# LCD-0_2.net
KiCad netlist of a schematic drawn in EAGLE
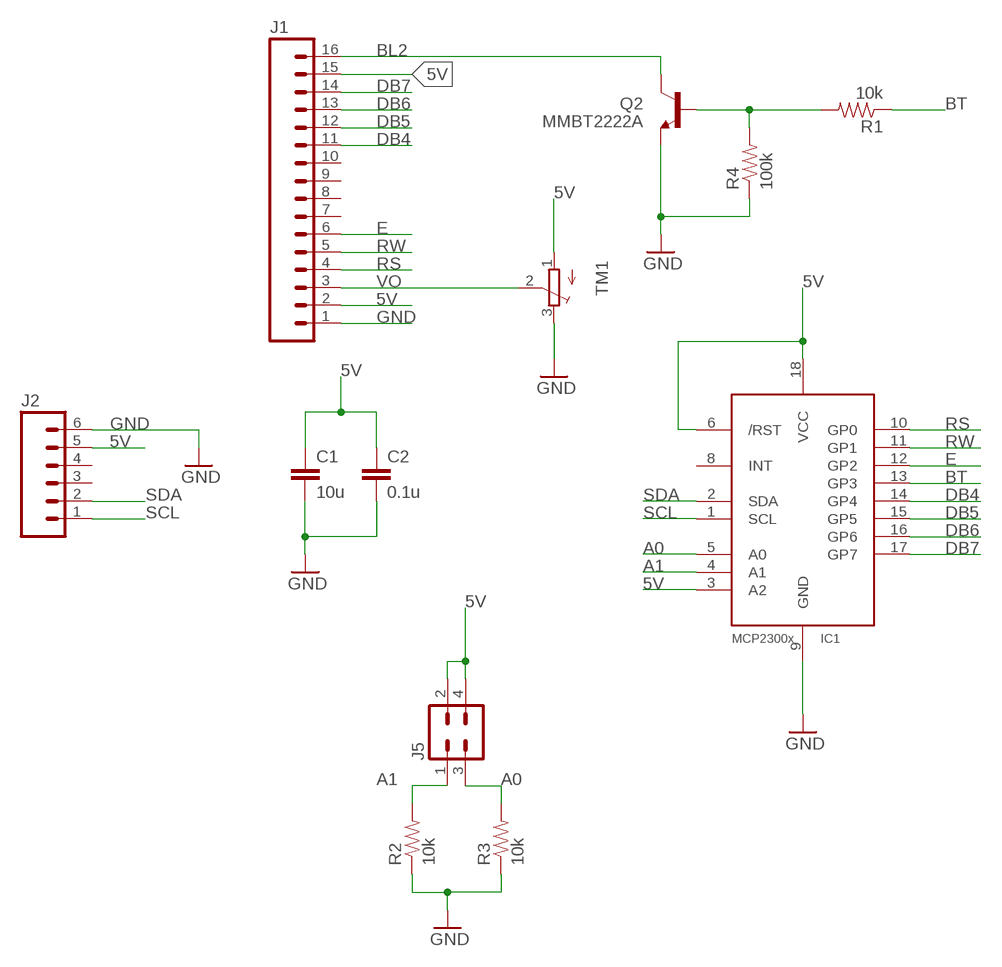
[diagram p0: schematic, sheet 1]

(export (version "E")
  (design (tool "Eeschema 10.0.6"))
  (components
    (comp (ref "C1")
      (value "10u")
      (footprint "eagle-import:0603-CAP")
      (libsource (lib "eagle-import") (part "CAP0603-CAP"))
    )
    (comp (ref "C2")
      (value "0.1u")
      (footprint "eagle-import:0603-CAP")
      (libsource (lib "eagle-import") (part "CAP0603-CAP"))
    )
    (comp (ref "IC1")
      (value "MCP23008/SO")
      (footprint "eagle-import:SO18W")
      (libsource (lib "eagle-import") (part "MCP23008/SO"))
    )
    (comp (ref "J1")
      (value "M16PTH")
      (footprint "eagle-import:1X16")
      (libsource (lib "eagle-import") (part "M16PTH"))
    )
    (comp (ref "J2")
      (value "M06RJ11")
      (footprint "eagle-import:RJ11-6P6C")
      (libsource (lib "eagle-import") (part "M06RJ11"))
    )
    (comp (ref "J5")
      (value "M02X2")
      (footprint "eagle-import:2X2")
      (libsource (lib "eagle-import") (part "M02X2"))
    )
    (comp (ref "Q2")
      (value "MMBT2222A")
      (footprint "eagle-import:SOT23-3")
      (libsource (lib "eagle-import") (part "TRANSISTOR_NPNMMBT2222A"))
    )
    (comp (ref "R1")
      (value "10k")
      (footprint "eagle-import:0603-RES")
      (libsource (lib "eagle-import") (part "RESISTOR0603"))
    )
    (comp (ref "R2")
      (value "10k")
      (footprint "eagle-import:0603-RES")
      (libsource (lib "eagle-import") (part "RESISTOR0603"))
    )
    (comp (ref "R3")
      (value "10k")
      (footprint "eagle-import:0603-RES")
      (libsource (lib "eagle-import") (part "RESISTOR0603"))
    )
    (comp (ref "R4")
      (value "100k")
      (footprint "eagle-import:0603-RES")
      (libsource (lib "eagle-import") (part "RESISTOR0603"))
    )
    (comp (ref "TM1")
      (value "TRIMPOTTC33X")
      (footprint "eagle-import:TC33X")
      (libsource (lib "eagle-import") (part "TRIMPOTTC33X"))
    )
  )
  (nets
    (net (code "1") (name "/A0") (class "Default")
      (node (ref "IC1") (pin "5") (pinfunction "A0_5") (pintype "input"))
      (node (ref "J5") (pin "3") (pinfunction "3_3") (pintype "passive"))
      (node (ref "R3") (pin "2") (pinfunction "2_2") (pintype "passive"))
    )
    (net (code "2") (name "/A1") (class "Default")
      (node (ref "IC1") (pin "4") (pinfunction "A1_4") (pintype "input"))
      (node (ref "J5") (pin "1") (pinfunction "1_1") (pintype "passive"))
      (node (ref "R2") (pin "2") (pinfunction "2_2") (pintype "passive"))
    )
    (net (code "3") (name "/BL2") (class "Default")
      (node (ref "J1") (pin "16") (pinfunction "16_16") (pintype "passive"))
      (node (ref "Q2") (pin "3") (pinfunction "C_3") (pintype "passive"))
    )
    (net (code "4") (name "/BT") (class "Default")
      (node (ref "IC1") (pin "13") (pinfunction "GP3_13") (pintype "bidirectional"))
      (node (ref "R1") (pin "1") (pinfunction "1_1") (pintype "passive"))
    )
    (net (code "5") (name "/DB4") (class "Default")
      (node (ref "IC1") (pin "14") (pinfunction "GP4_14") (pintype "bidirectional"))
      (node (ref "J1") (pin "11") (pinfunction "11_11") (pintype "passive"))
    )
    (net (code "6") (name "/DB5") (class "Default")
      (node (ref "IC1") (pin "15") (pinfunction "GP5_15") (pintype "bidirectional"))
      (node (ref "J1") (pin "12") (pinfunction "12_12") (pintype "passive"))
    )
    (net (code "7") (name "/DB6") (class "Default")
      (node (ref "IC1") (pin "16") (pinfunction "GP6_16") (pintype "bidirectional"))
      (node (ref "J1") (pin "13") (pinfunction "13_13") (pintype "passive"))
    )
    (net (code "8") (name "/DB7") (class "Default")
      (node (ref "IC1") (pin "17") (pinfunction "GP7_17") (pintype "bidirectional"))
      (node (ref "J1") (pin "14") (pinfunction "14_14") (pintype "passive"))
    )
    (net (code "9") (name "/E") (class "Default")
      (node (ref "IC1") (pin "12") (pinfunction "GP2_12") (pintype "bidirectional"))
      (node (ref "J1") (pin "6") (pinfunction "6_6") (pintype "passive"))
    )
    (net (code "10") (name "/RS") (class "Default")
      (node (ref "IC1") (pin "10") (pinfunction "GP0_10") (pintype "bidirectional"))
      (node (ref "J1") (pin "4") (pinfunction "4_4") (pintype "passive"))
    )
    (net (code "11") (name "/RW") (class "Default")
      (node (ref "IC1") (pin "11") (pinfunction "GP1_11") (pintype "bidirectional"))
      (node (ref "J1") (pin "5") (pinfunction "5_5") (pintype "passive"))
    )
    (net (code "12") (name "/SCL") (class "Default")
      (node (ref "IC1") (pin "1") (pinfunction "SCL_1") (pintype "bidirectional"))
      (node (ref "J2") (pin "1") (pinfunction "1_1") (pintype "passive"))
    )
    (net (code "13") (name "/SDA") (class "Default")
      (node (ref "IC1") (pin "2") (pinfunction "SDA_2") (pintype "bidirectional"))
      (node (ref "J2") (pin "2") (pinfunction "2_2") (pintype "passive"))
    )
    (net (code "14") (name "/VO") (class "Default")
      (node (ref "J1") (pin "3") (pinfunction "3_3") (pintype "passive"))
      (node (ref "TM1") (pin "2") (pinfunction "S_2") (pintype "passive"))
    )
    (net (code "15") (name "5V") (class "Default")
      (node (ref "C1") (pin "1") (pinfunction "1_1") (pintype "passive"))
      (node (ref "C2") (pin "1") (pinfunction "1_1") (pintype "passive"))
      (node (ref "IC1") (pin "18") (pinfunction "VCC_18") (pintype "power_in"))
      (node (ref "IC1") (pin "3") (pinfunction "A2_3") (pintype "input"))
      (node (ref "IC1") (pin "6") (pinfunction "/RST_6") (pintype "input"))
      (node (ref "J1") (pin "15") (pinfunction "15_15") (pintype "passive"))
      (node (ref "J1") (pin "2") (pinfunction "2_2") (pintype "passive"))
      (node (ref "J2") (pin "5") (pinfunction "5_5") (pintype "passive"))
      (node (ref "J5") (pin "2") (pinfunction "2_2") (pintype "passive"))
      (node (ref "J5") (pin "4") (pinfunction "4_4") (pintype "passive"))
      (node (ref "TM1") (pin "1") (pinfunction "A_1") (pintype "passive"))
    )
    (net (code "16") (name "GND") (class "Default")
      (node (ref "C1") (pin "2") (pinfunction "2_2") (pintype "passive"))
      (node (ref "C2") (pin "2") (pinfunction "2_2") (pintype "passive"))
      (node (ref "IC1") (pin "9") (pinfunction "GND_9") (pintype "power_in"))
      (node (ref "J1") (pin "1") (pinfunction "1_1") (pintype "passive"))
      (node (ref "J2") (pin "6") (pinfunction "6_6") (pintype "passive"))
      (node (ref "Q2") (pin "2") (pinfunction "E_2") (pintype "passive"))
      (node (ref "R2") (pin "1") (pinfunction "1_1") (pintype "passive"))
      (node (ref "R3") (pin "1") (pinfunction "1_1") (pintype "passive"))
      (node (ref "R4") (pin "1") (pinfunction "1_1") (pintype "passive"))
      (node (ref "TM1") (pin "3") (pinfunction "E_3") (pintype "passive"))
    )
    (net (code "17") (name "Net-(Q2-B)") (class "Default")
      (node (ref "Q2") (pin "1") (pinfunction "B_1") (pintype "passive"))
      (node (ref "R1") (pin "2") (pinfunction "2_2") (pintype "passive"))
      (node (ref "R4") (pin "2") (pinfunction "2_2") (pintype "passive"))
    )
    (net (code "18") (name "unconnected-(IC1-INT-Pad8)") (class "Default")
      (node (ref "IC1") (pin "8") (pinfunction "INT_8") (pintype "output"))
    )
    (net (code "19") (name "unconnected-(J1-Pad7)") (class "Default")
      (node (ref "J1") (pin "7") (pinfunction "7_7") (pintype "passive"))
    )
    (net (code "20") (name "unconnected-(J1-Pad8)") (class "Default")
      (node (ref "J1") (pin "8") (pinfunction "8_8") (pintype "passive"))
    )
    (net (code "21") (name "unconnected-(J1-Pad9)") (class "Default")
      (node (ref "J1") (pin "9") (pinfunction "9_9") (pintype "passive"))
    )
    (net (code "22") (name "unconnected-(J1-Pad10)") (class "Default")
      (node (ref "J1") (pin "10") (pinfunction "10_10") (pintype "passive"))
    )
    (net (code "23") (name "unconnected-(J2-Pad3)") (class "Default")
      (node (ref "J2") (pin "3") (pinfunction "3_3") (pintype "passive"))
    )
    (net (code "24") (name "unconnected-(J2-Pad4)") (class "Default")
      (node (ref "J2") (pin "4") (pinfunction "4_4") (pintype "passive"))
    )
  )
)
